# nodemcuPowerSupply.net
KiCad netlist of a schematic drawn in EAGLE
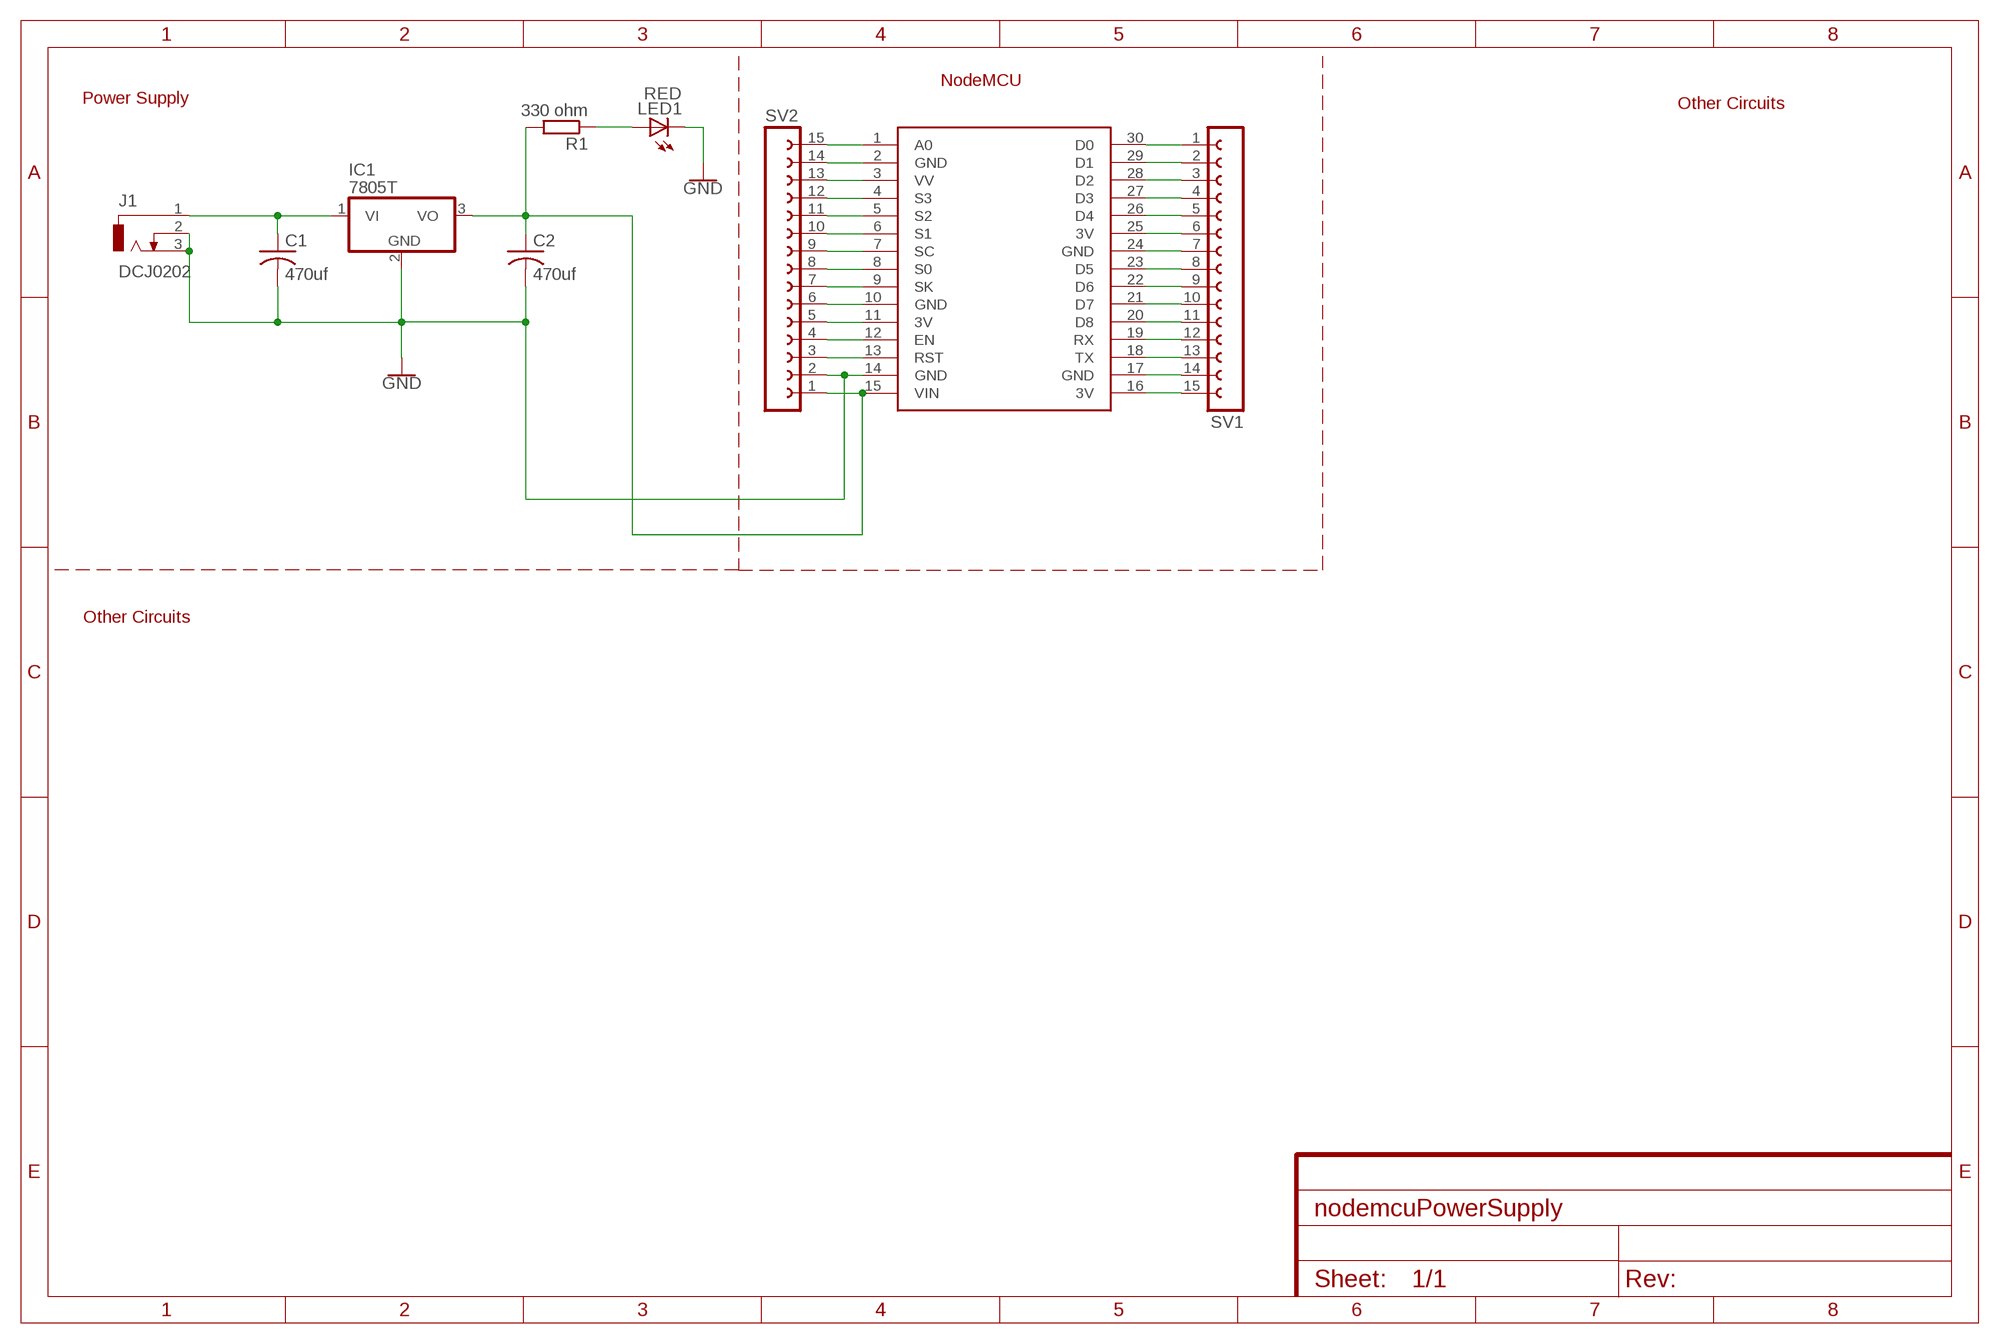
[diagram p0: schematic, sheet 1]

(export (version "E")
  (design (tool "Eeschema 10.0.6"))
  (components
    (comp (ref "C1")
      (value "470uf")
      (footprint "eagle-import:C025-024X044")
      (libsource (lib "eagle-import") (part "C-US025-024X044"))
    )
    (comp (ref "C2")
      (value "470uf")
      (footprint "eagle-import:C025-024X044")
      (libsource (lib "eagle-import") (part "C-US025-024X044"))
    )
    (comp (ref "IC1")
      (value "7805T")
      (footprint "eagle-import:TO220H")
      (libsource (lib "eagle-import") (part "78T05"))
    )
    (comp (ref "J1")
      (value "DCJ0202")
      (footprint "eagle-import:DCJ0202")
      (libsource (lib "eagle-import") (part "DCJ0202"))
    )
    (comp (ref "LED1")
      (value "RED")
      (footprint "eagle-import:LED3MM")
      (libsource (lib "eagle-import") (part "LED3MM"))
    )
    (comp (ref "R1")
      (value "330 ohm")
      (footprint "eagle-import:0204_5")
      (libsource (lib "eagle-import") (part "R-EU_0204/5"))
    )
    (comp (ref "SV1")
      (value "FE15-1")
      (footprint "eagle-import:FE15")
      (libsource (lib "eagle-import") (part "FE15-1"))
    )
    (comp (ref "SV2")
      (value "FE15-1")
      (footprint "eagle-import:FE15")
      (libsource (lib "eagle-import") (part "FE15-1"))
    )
    (comp (ref "U$1")
      (value "NODEMCU")
      (footprint "eagle-import:NODEMCU")
      (libsource (lib "eagle-import") (part "NODEMCU"))
    )
  )
  (nets
    (net (code "1") (name "GND") (class "Default")
      (node (ref "C1") (pin "2") (pinfunction "2_2") (pintype "passive"))
      (node (ref "C2") (pin "2") (pinfunction "2_2") (pintype "passive"))
      (node (ref "IC1") (pin "2") (pinfunction "GND_2") (pintype "passive"))
      (node (ref "J1") (pin "2") (pinfunction "2_2") (pintype "passive"))
      (node (ref "J1") (pin "3") (pinfunction "3_3") (pintype "passive"))
      (node (ref "LED1") (pin "K") (pinfunction "C_K") (pintype "passive"))
      (node (ref "SV2") (pin "2") (pinfunction "2_2") (pintype "passive"))
      (node (ref "U$1") (pin "14") (pinfunction "GND_14") (pintype "power_in"))
    )
    (net (code "2") (name "Net-(IC1-VI)") (class "Default")
      (node (ref "C1") (pin "1") (pinfunction "1_1") (pintype "passive"))
      (node (ref "IC1") (pin "1") (pinfunction "VI_1") (pintype "input"))
      (node (ref "J1") (pin "1") (pinfunction "1_1") (pintype "passive"))
    )
    (net (code "3") (name "Net-(IC1-VO)") (class "Default")
      (node (ref "C2") (pin "1") (pinfunction "1_1") (pintype "passive"))
      (node (ref "IC1") (pin "3") (pinfunction "VO_3") (pintype "passive"))
      (node (ref "R1") (pin "2") (pinfunction "2_2") (pintype "passive"))
      (node (ref "SV2") (pin "1") (pinfunction "1_1") (pintype "passive"))
      (node (ref "U$1") (pin "15") (pinfunction "VIN_15") (pintype "bidirectional"))
    )
    (net (code "4") (name "Net-(LED1-PadA)") (class "Default")
      (node (ref "LED1") (pin "A") (pinfunction "A_A") (pintype "passive"))
      (node (ref "R1") (pin "1") (pinfunction "1_1") (pintype "passive"))
    )
    (net (code "5") (name "Net-(SV1-Pad6)") (class "Default")
      (node (ref "SV1") (pin "6") (pinfunction "6_6") (pintype "passive"))
      (node (ref "U$1") (pin "25") (pinfunction "3V_25") (pintype "power_in"))
    )
    (net (code "6") (name "Net-(SV1-Pad7)") (class "Default")
      (node (ref "SV1") (pin "7") (pinfunction "7_7") (pintype "passive"))
      (node (ref "U$1") (pin "24") (pinfunction "GND_24") (pintype "power_in"))
    )
    (net (code "7") (name "Net-(SV1-Pad14)") (class "Default")
      (node (ref "SV1") (pin "14") (pinfunction "14_14") (pintype "passive"))
      (node (ref "U$1") (pin "17") (pinfunction "GND_17") (pintype "power_in"))
    )
    (net (code "8") (name "Net-(SV1-Pad15)") (class "Default")
      (node (ref "SV1") (pin "15") (pinfunction "15_15") (pintype "passive"))
      (node (ref "U$1") (pin "16") (pinfunction "3V_16") (pintype "power_in"))
    )
    (net (code "9") (name "Net-(SV2-Pad5)") (class "Default")
      (node (ref "SV2") (pin "5") (pinfunction "5_5") (pintype "passive"))
      (node (ref "U$1") (pin "11") (pinfunction "3V_11") (pintype "power_in"))
    )
    (net (code "10") (name "Net-(SV2-Pad6)") (class "Default")
      (node (ref "SV2") (pin "6") (pinfunction "6_6") (pintype "passive"))
      (node (ref "U$1") (pin "10") (pinfunction "GND_10") (pintype "power_in"))
    )
    (net (code "11") (name "Net-(SV2-Pad14)") (class "Default")
      (node (ref "SV2") (pin "14") (pinfunction "14_14") (pintype "passive"))
      (node (ref "U$1") (pin "2") (pinfunction "GND_2") (pintype "power_in"))
    )
    (net (code "12") (name "Net-(U$1-A0)") (class "Default")
      (node (ref "SV2") (pin "15") (pinfunction "15_15") (pintype "passive"))
      (node (ref "U$1") (pin "1") (pinfunction "A0_1") (pintype "bidirectional"))
    )
    (net (code "13") (name "Net-(U$1-D0)") (class "Default")
      (node (ref "SV1") (pin "1") (pinfunction "1_1") (pintype "passive"))
      (node (ref "U$1") (pin "30") (pinfunction "D0_30") (pintype "bidirectional"))
    )
    (net (code "14") (name "Net-(U$1-D1)") (class "Default")
      (node (ref "SV1") (pin "2") (pinfunction "2_2") (pintype "passive"))
      (node (ref "U$1") (pin "29") (pinfunction "D1_29") (pintype "bidirectional"))
    )
    (net (code "15") (name "Net-(U$1-D2)") (class "Default")
      (node (ref "SV1") (pin "3") (pinfunction "3_3") (pintype "passive"))
      (node (ref "U$1") (pin "28") (pinfunction "D2_28") (pintype "bidirectional"))
    )
    (net (code "16") (name "Net-(U$1-D3)") (class "Default")
      (node (ref "SV1") (pin "4") (pinfunction "4_4") (pintype "passive"))
      (node (ref "U$1") (pin "27") (pinfunction "D3_27") (pintype "bidirectional"))
    )
    (net (code "17") (name "Net-(U$1-D4)") (class "Default")
      (node (ref "SV1") (pin "5") (pinfunction "5_5") (pintype "passive"))
      (node (ref "U$1") (pin "26") (pinfunction "D4_26") (pintype "bidirectional"))
    )
    (net (code "18") (name "Net-(U$1-D5)") (class "Default")
      (node (ref "SV1") (pin "8") (pinfunction "8_8") (pintype "passive"))
      (node (ref "U$1") (pin "23") (pinfunction "D5_23") (pintype "bidirectional"))
    )
    (net (code "19") (name "Net-(U$1-D6)") (class "Default")
      (node (ref "SV1") (pin "9") (pinfunction "9_9") (pintype "passive"))
      (node (ref "U$1") (pin "22") (pinfunction "D6_22") (pintype "bidirectional"))
    )
    (net (code "20") (name "Net-(U$1-D7)") (class "Default")
      (node (ref "SV1") (pin "10") (pinfunction "10_10") (pintype "passive"))
      (node (ref "U$1") (pin "21") (pinfunction "D7_21") (pintype "bidirectional"))
    )
    (net (code "21") (name "Net-(U$1-D8)") (class "Default")
      (node (ref "SV1") (pin "11") (pinfunction "11_11") (pintype "passive"))
      (node (ref "U$1") (pin "20") (pinfunction "D8_20") (pintype "bidirectional"))
    )
    (net (code "22") (name "Net-(U$1-EN)") (class "Default")
      (node (ref "SV2") (pin "4") (pinfunction "4_4") (pintype "passive"))
      (node (ref "U$1") (pin "12") (pinfunction "EN_12") (pintype "bidirectional"))
    )
    (net (code "23") (name "Net-(U$1-RST)") (class "Default")
      (node (ref "SV2") (pin "3") (pinfunction "3_3") (pintype "passive"))
      (node (ref "U$1") (pin "13") (pinfunction "RST_13") (pintype "bidirectional"))
    )
    (net (code "24") (name "Net-(U$1-RX)") (class "Default")
      (node (ref "SV1") (pin "12") (pinfunction "12_12") (pintype "passive"))
      (node (ref "U$1") (pin "19") (pinfunction "RX_19") (pintype "bidirectional"))
    )
    (net (code "25") (name "Net-(U$1-S0)") (class "Default")
      (node (ref "SV2") (pin "8") (pinfunction "8_8") (pintype "passive"))
      (node (ref "U$1") (pin "8") (pinfunction "S0_8") (pintype "bidirectional"))
    )
    (net (code "26") (name "Net-(U$1-S1)") (class "Default")
      (node (ref "SV2") (pin "10") (pinfunction "10_10") (pintype "passive"))
      (node (ref "U$1") (pin "6") (pinfunction "S1_6") (pintype "bidirectional"))
    )
    (net (code "27") (name "Net-(U$1-S2)") (class "Default")
      (node (ref "SV2") (pin "11") (pinfunction "11_11") (pintype "passive"))
      (node (ref "U$1") (pin "5") (pinfunction "S2_5") (pintype "bidirectional"))
    )
    (net (code "28") (name "Net-(U$1-S3)") (class "Default")
      (node (ref "SV2") (pin "12") (pinfunction "12_12") (pintype "passive"))
      (node (ref "U$1") (pin "4") (pinfunction "S3_4") (pintype "bidirectional"))
    )
    (net (code "29") (name "Net-(U$1-SC)") (class "Default")
      (node (ref "SV2") (pin "9") (pinfunction "9_9") (pintype "passive"))
      (node (ref "U$1") (pin "7") (pinfunction "SC_7") (pintype "bidirectional"))
    )
    (net (code "30") (name "Net-(U$1-SK)") (class "Default")
      (node (ref "SV2") (pin "7") (pinfunction "7_7") (pintype "passive"))
      (node (ref "U$1") (pin "9") (pinfunction "SK_9") (pintype "bidirectional"))
    )
    (net (code "31") (name "Net-(U$1-TX)") (class "Default")
      (node (ref "SV1") (pin "13") (pinfunction "13_13") (pintype "passive"))
      (node (ref "U$1") (pin "18") (pinfunction "TX_18") (pintype "bidirectional"))
    )
    (net (code "32") (name "Net-(U$1-VV)") (class "Default")
      (node (ref "SV2") (pin "13") (pinfunction "13_13") (pintype "passive"))
      (node (ref "U$1") (pin "3") (pinfunction "VV_3") (pintype "bidirectional"))
    )
  )
)
